# PIC18LF67K40-breakout.net
KiCad netlist of a schematic drawn in EAGLE
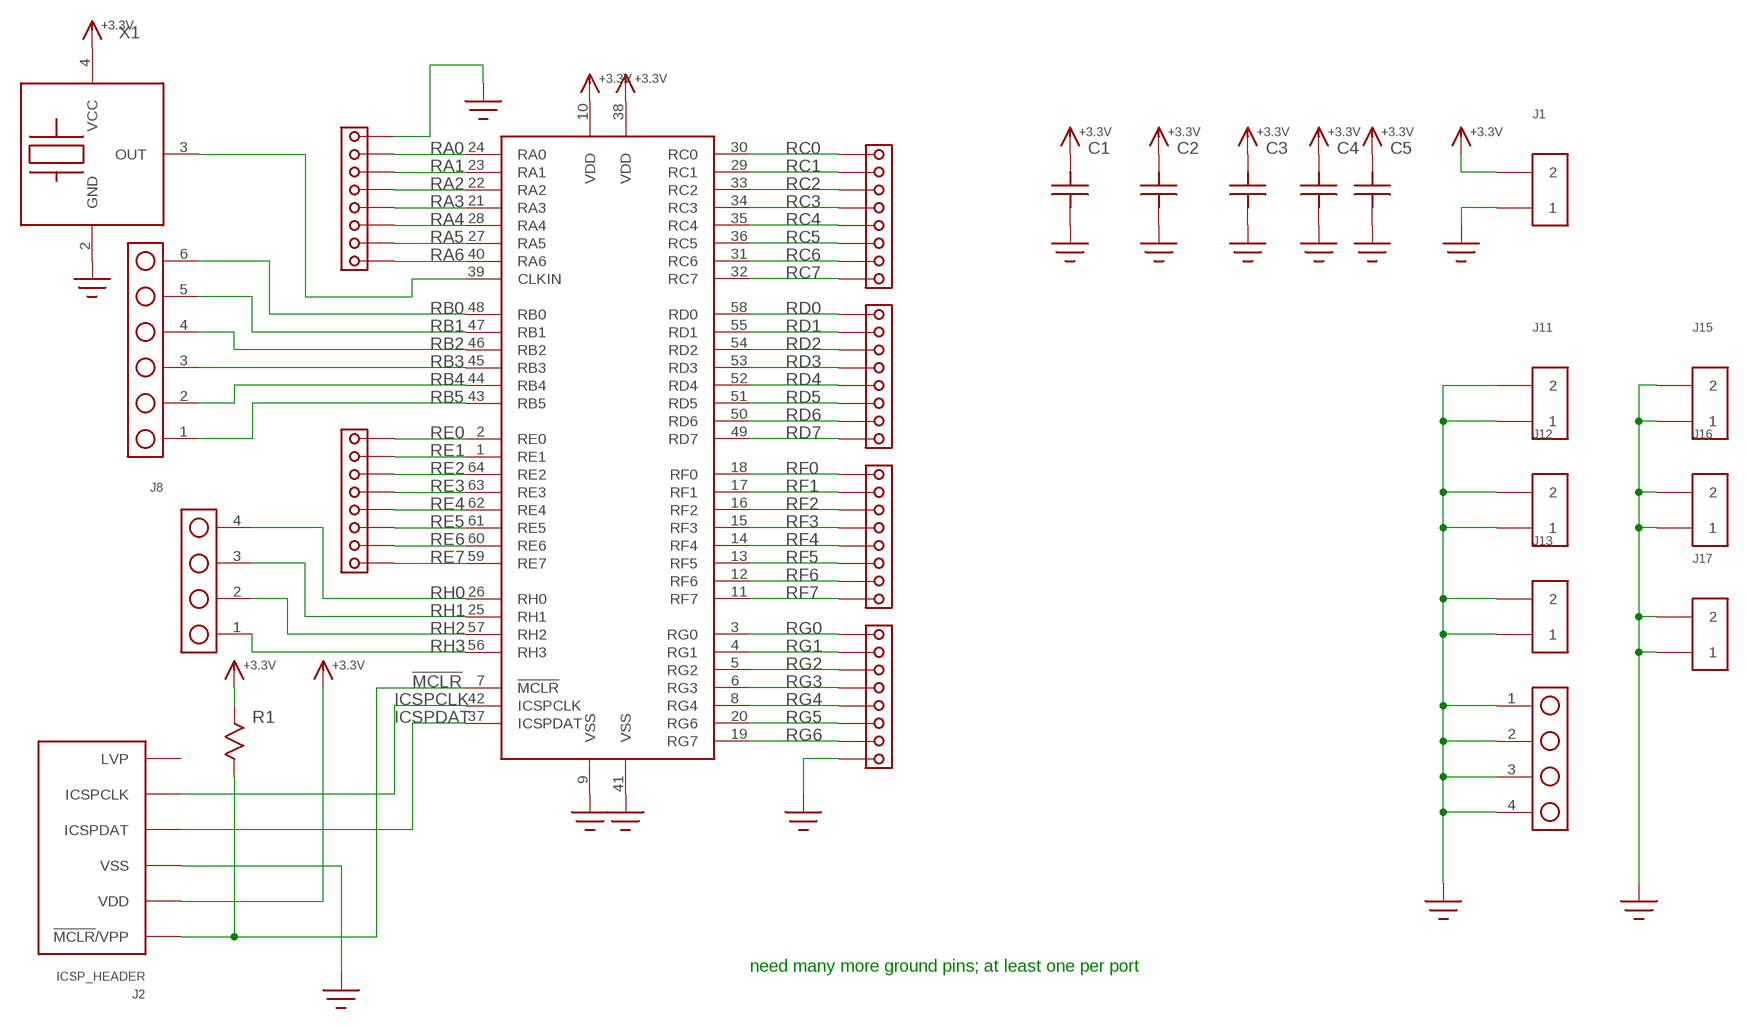
[diagram p0: schematic, sheet 1]

(export (version "E")
  (design (tool "Eeschema 10.0.6"))
  (components
    (comp (ref "C1")
      (value "C1206")
      (footprint "eagle-import:1206")
      (libsource (lib "eagle-import") (part "C1206"))
    )
    (comp (ref "C2")
      (value "C1206")
      (footprint "eagle-import:1206")
      (libsource (lib "eagle-import") (part "C1206"))
    )
    (comp (ref "C3")
      (value "C0603")
      (footprint "eagle-import:C0603")
      (libsource (lib "eagle-import") (part "C0603"))
    )
    (comp (ref "C4")
      (value "C0603")
      (footprint "eagle-import:C0603")
      (libsource (lib "eagle-import") (part "C0603"))
    )
    (comp (ref "C5")
      (value "C0603")
      (footprint "eagle-import:C0603")
      (libsource (lib "eagle-import") (part "C0603"))
    )
    (comp (ref "IC1")
      (value "PIC18LF67K40")
      (footprint "eagle-import:TQFP-100-10X10")
      (libsource (lib "eagle-import") (part "PIC18LF67K40"))
    )
    (comp (ref "J1")
      (value "HEADER_2PIN")
      (footprint "eagle-import:HEADER_2PIN")
      (libsource (lib "eagle-import") (part "HEADER_2PIN"))
    )
    (comp (ref "J2")
      (value "ICSP_HEADER")
      (footprint "eagle-import:HEADER_6PIN")
      (libsource (lib "eagle-import") (part "ICSP_HEADER"))
    )
    (comp (ref "J3")
      (value "HEADER_8PIN_TIGHT")
      (footprint "eagle-import:HEADER_8_PIN")
      (libsource (lib "eagle-import") (part "HEADER_8PIN_TIGHT"))
    )
    (comp (ref "J4")
      (value "HEADER_8PIN_TIGHT")
      (footprint "eagle-import:HEADER_8_PIN")
      (libsource (lib "eagle-import") (part "HEADER_8PIN_TIGHT"))
    )
    (comp (ref "J5")
      (value "HEADER_8PIN_TIGHT")
      (footprint "eagle-import:HEADER_8_PIN")
      (libsource (lib "eagle-import") (part "HEADER_8PIN_TIGHT"))
    )
    (comp (ref "J6")
      (value "HEADER_8PIN_TIGHT")
      (footprint "eagle-import:HEADER_8_PIN")
      (libsource (lib "eagle-import") (part "HEADER_8PIN_TIGHT"))
    )
    (comp (ref "J7")
      (value "HEADER_8PIN_TIGHT")
      (footprint "eagle-import:HEADER_8_PIN")
      (libsource (lib "eagle-import") (part "HEADER_8PIN_TIGHT"))
    )
    (comp (ref "J8")
      (value "HEADER_6PIN")
      (footprint "eagle-import:HEADER_6PIN")
      (libsource (lib "eagle-import") (part "HEADER_6PIN"))
    )
    (comp (ref "J9")
      (value "HEADER_4PIN")
      (footprint "eagle-import:HEADER_4PIN")
      (libsource (lib "eagle-import") (part "HEADER_4PIN"))
    )
    (comp (ref "J10")
      (value "HEADER_8PIN_TIGHT")
      (footprint "eagle-import:HEADER_8_PIN")
      (libsource (lib "eagle-import") (part "HEADER_8PIN_TIGHT"))
    )
    (comp (ref "J11")
      (value "HEADER_2PIN")
      (footprint "eagle-import:HEADER_2PIN")
      (libsource (lib "eagle-import") (part "HEADER_2PIN"))
    )
    (comp (ref "J12")
      (value "HEADER_2PIN")
      (footprint "eagle-import:HEADER_2PIN")
      (libsource (lib "eagle-import") (part "HEADER_2PIN"))
    )
    (comp (ref "J13")
      (value "HEADER_2PIN")
      (footprint "eagle-import:HEADER_2PIN")
      (libsource (lib "eagle-import") (part "HEADER_2PIN"))
    )
    (comp (ref "J14")
      (value "HEADER_4PIN")
      (footprint "eagle-import:HEADER_4PIN")
      (libsource (lib "eagle-import") (part "HEADER_4PIN"))
    )
    (comp (ref "J15")
      (value "HEADER_2PIN")
      (footprint "eagle-import:HEADER_2PIN")
      (libsource (lib "eagle-import") (part "HEADER_2PIN"))
    )
    (comp (ref "J16")
      (value "HEADER_2PIN")
      (footprint "eagle-import:HEADER_2PIN")
      (libsource (lib "eagle-import") (part "HEADER_2PIN"))
    )
    (comp (ref "J17")
      (value "HEADER_2PIN")
      (footprint "eagle-import:HEADER_2PIN")
      (libsource (lib "eagle-import") (part "HEADER_2PIN"))
    )
    (comp (ref "R1")
      (value "R0603")
      (footprint "eagle-import:R0603")
      (libsource (lib "eagle-import") (part "R0603"))
    )
    (comp (ref "X1")
      (value "XTAL_OSC")
      (footprint "eagle-import:XTAL_3.2X5")
      (libsource (lib "eagle-import") (part "XTAL_OSC"))
    )
  )
  (nets
    (net (code "1") (name "+3.3V") (class "Default")
      (node (ref "C1") (pin "P$2") (pinfunction "P$2_P$2") (pintype "bidirectional"))
      (node (ref "C2") (pin "P$2") (pinfunction "P$2_P$2") (pintype "bidirectional"))
      (node (ref "C3") (pin "P$2") (pinfunction "P$2_P$2") (pintype "bidirectional"))
      (node (ref "C4") (pin "P$2") (pinfunction "P$2_P$2") (pintype "bidirectional"))
      (node (ref "C5") (pin "P$2") (pinfunction "P$2_P$2") (pintype "bidirectional"))
      (node (ref "IC1") (pin "10") (pinfunction "VDD_10") (pintype "bidirectional"))
      (node (ref "IC1") (pin "38") (pinfunction "VDD_38") (pintype "bidirectional"))
      (node (ref "J1") (pin "2") (pinfunction "2_2") (pintype "bidirectional"))
      (node (ref "J2") (pin "2") (pinfunction "VDD_2") (pintype "bidirectional"))
      (node (ref "R1") (pin "P$1") (pinfunction "P$3_P$1") (pintype "bidirectional"))
      (node (ref "X1") (pin "4") (pinfunction "VCC_4") (pintype "bidirectional"))
    )
    (net (code "2") (name "/ICSPCLK") (class "Default")
      (node (ref "IC1") (pin "42") (pinfunction "ICSPCLK_42") (pintype "bidirectional"))
      (node (ref "J2") (pin "5") (pinfunction "ICSPCLK_5") (pintype "bidirectional"))
    )
    (net (code "3") (name "/ICSPDAT") (class "Default")
      (node (ref "IC1") (pin "37") (pinfunction "ICSPDAT_37") (pintype "bidirectional"))
      (node (ref "J2") (pin "4") (pinfunction "ICSPDAT_4") (pintype "bidirectional"))
    )
    (net (code "4") (name "/RA0") (class "Default")
      (node (ref "IC1") (pin "24") (pinfunction "RA0_24") (pintype "bidirectional"))
      (node (ref "J6") (pin "7") (pinfunction "7_7") (pintype "bidirectional"))
    )
    (net (code "5") (name "/RA1") (class "Default")
      (node (ref "IC1") (pin "23") (pinfunction "RA1_23") (pintype "bidirectional"))
      (node (ref "J6") (pin "6") (pinfunction "6_6") (pintype "bidirectional"))
    )
    (net (code "6") (name "/RA2") (class "Default")
      (node (ref "IC1") (pin "22") (pinfunction "RA2_22") (pintype "bidirectional"))
      (node (ref "J6") (pin "5") (pinfunction "5_5") (pintype "bidirectional"))
    )
    (net (code "7") (name "/RA3") (class "Default")
      (node (ref "IC1") (pin "21") (pinfunction "RA3_21") (pintype "bidirectional"))
      (node (ref "J6") (pin "4") (pinfunction "4_4") (pintype "bidirectional"))
    )
    (net (code "8") (name "/RA4") (class "Default")
      (node (ref "IC1") (pin "28") (pinfunction "RA4_28") (pintype "bidirectional"))
      (node (ref "J6") (pin "3") (pinfunction "3_3") (pintype "bidirectional"))
    )
    (net (code "9") (name "/RA5") (class "Default")
      (node (ref "IC1") (pin "27") (pinfunction "RA5_27") (pintype "bidirectional"))
      (node (ref "J6") (pin "2") (pinfunction "2_2") (pintype "bidirectional"))
    )
    (net (code "10") (name "/RA6") (class "Default")
      (node (ref "IC1") (pin "40") (pinfunction "RA6_40") (pintype "bidirectional"))
      (node (ref "J6") (pin "1") (pinfunction "1_1") (pintype "bidirectional"))
    )
    (net (code "11") (name "/RB0") (class "Default")
      (node (ref "IC1") (pin "48") (pinfunction "RB0_48") (pintype "bidirectional"))
      (node (ref "J8") (pin "6") (pinfunction "6_6") (pintype "bidirectional"))
    )
    (net (code "12") (name "/RB1") (class "Default")
      (node (ref "IC1") (pin "47") (pinfunction "RB1_47") (pintype "bidirectional"))
      (node (ref "J8") (pin "5") (pinfunction "5_5") (pintype "bidirectional"))
    )
    (net (code "13") (name "/RB2") (class "Default")
      (node (ref "IC1") (pin "46") (pinfunction "RB2_46") (pintype "bidirectional"))
      (node (ref "J8") (pin "4") (pinfunction "4_4") (pintype "bidirectional"))
    )
    (net (code "14") (name "/RB3") (class "Default")
      (node (ref "IC1") (pin "45") (pinfunction "RB3_45") (pintype "bidirectional"))
      (node (ref "J8") (pin "3") (pinfunction "3_3") (pintype "bidirectional"))
    )
    (net (code "15") (name "/RB4") (class "Default")
      (node (ref "IC1") (pin "44") (pinfunction "RB4_44") (pintype "bidirectional"))
      (node (ref "J8") (pin "2") (pinfunction "2_2") (pintype "bidirectional"))
    )
    (net (code "16") (name "/RB5") (class "Default")
      (node (ref "IC1") (pin "43") (pinfunction "RB5_43") (pintype "bidirectional"))
      (node (ref "J8") (pin "1") (pinfunction "1_1") (pintype "bidirectional"))
    )
    (net (code "17") (name "/RC0") (class "Default")
      (node (ref "IC1") (pin "30") (pinfunction "RC0_30") (pintype "bidirectional"))
      (node (ref "J3") (pin "1") (pinfunction "1_1") (pintype "bidirectional"))
    )
    (net (code "18") (name "/RC1") (class "Default")
      (node (ref "IC1") (pin "29") (pinfunction "RC1_29") (pintype "bidirectional"))
      (node (ref "J3") (pin "2") (pinfunction "2_2") (pintype "bidirectional"))
    )
    (net (code "19") (name "/RC2") (class "Default")
      (node (ref "IC1") (pin "33") (pinfunction "RC2_33") (pintype "bidirectional"))
      (node (ref "J3") (pin "3") (pinfunction "3_3") (pintype "bidirectional"))
    )
    (net (code "20") (name "/RC3") (class "Default")
      (node (ref "IC1") (pin "34") (pinfunction "RC3_34") (pintype "bidirectional"))
      (node (ref "J3") (pin "4") (pinfunction "4_4") (pintype "bidirectional"))
    )
    (net (code "21") (name "/RC4") (class "Default")
      (node (ref "IC1") (pin "35") (pinfunction "RC4_35") (pintype "bidirectional"))
      (node (ref "J3") (pin "5") (pinfunction "5_5") (pintype "bidirectional"))
    )
    (net (code "22") (name "/RC5") (class "Default")
      (node (ref "IC1") (pin "36") (pinfunction "RC5_36") (pintype "bidirectional"))
      (node (ref "J3") (pin "6") (pinfunction "6_6") (pintype "bidirectional"))
    )
    (net (code "23") (name "/RC6") (class "Default")
      (node (ref "IC1") (pin "31") (pinfunction "RC6_31") (pintype "bidirectional"))
      (node (ref "J3") (pin "7") (pinfunction "7_7") (pintype "bidirectional"))
    )
    (net (code "24") (name "/RC7") (class "Default")
      (node (ref "IC1") (pin "32") (pinfunction "RC7_32") (pintype "bidirectional"))
      (node (ref "J3") (pin "8") (pinfunction "8_8") (pintype "bidirectional"))
    )
    (net (code "25") (name "/RD0") (class "Default")
      (node (ref "IC1") (pin "58") (pinfunction "RD0_58") (pintype "bidirectional"))
      (node (ref "J4") (pin "1") (pinfunction "1_1") (pintype "bidirectional"))
    )
    (net (code "26") (name "/RD1") (class "Default")
      (node (ref "IC1") (pin "55") (pinfunction "RD1_55") (pintype "bidirectional"))
      (node (ref "J4") (pin "2") (pinfunction "2_2") (pintype "bidirectional"))
    )
    (net (code "27") (name "/RD2") (class "Default")
      (node (ref "IC1") (pin "54") (pinfunction "RD2_54") (pintype "bidirectional"))
      (node (ref "J4") (pin "3") (pinfunction "3_3") (pintype "bidirectional"))
    )
    (net (code "28") (name "/RD3") (class "Default")
      (node (ref "IC1") (pin "53") (pinfunction "RD3_53") (pintype "bidirectional"))
      (node (ref "J4") (pin "4") (pinfunction "4_4") (pintype "bidirectional"))
    )
    (net (code "29") (name "/RD4") (class "Default")
      (node (ref "IC1") (pin "52") (pinfunction "RD4_52") (pintype "bidirectional"))
      (node (ref "J4") (pin "5") (pinfunction "5_5") (pintype "bidirectional"))
    )
    (net (code "30") (name "/RD5") (class "Default")
      (node (ref "IC1") (pin "51") (pinfunction "RD5_51") (pintype "bidirectional"))
      (node (ref "J4") (pin "6") (pinfunction "6_6") (pintype "bidirectional"))
    )
    (net (code "31") (name "/RD6") (class "Default")
      (node (ref "IC1") (pin "50") (pinfunction "RD6_50") (pintype "bidirectional"))
      (node (ref "J4") (pin "7") (pinfunction "7_7") (pintype "bidirectional"))
    )
    (net (code "32") (name "/RD7") (class "Default")
      (node (ref "IC1") (pin "49") (pinfunction "RD7_49") (pintype "bidirectional"))
      (node (ref "J4") (pin "8") (pinfunction "8_8") (pintype "bidirectional"))
    )
    (net (code "33") (name "/RE0") (class "Default")
      (node (ref "IC1") (pin "2") (pinfunction "RE0_2") (pintype "bidirectional"))
      (node (ref "J7") (pin "8") (pinfunction "8_8") (pintype "bidirectional"))
    )
    (net (code "34") (name "/RE1") (class "Default")
      (node (ref "IC1") (pin "1") (pinfunction "RE1_1") (pintype "bidirectional"))
      (node (ref "J7") (pin "7") (pinfunction "7_7") (pintype "bidirectional"))
    )
    (net (code "35") (name "/RE2") (class "Default")
      (node (ref "IC1") (pin "64") (pinfunction "RE2_64") (pintype "bidirectional"))
      (node (ref "J7") (pin "6") (pinfunction "6_6") (pintype "bidirectional"))
    )
    (net (code "36") (name "/RE3") (class "Default")
      (node (ref "IC1") (pin "63") (pinfunction "RE3_63") (pintype "bidirectional"))
      (node (ref "J7") (pin "5") (pinfunction "5_5") (pintype "bidirectional"))
    )
    (net (code "37") (name "/RE4") (class "Default")
      (node (ref "IC1") (pin "62") (pinfunction "RE4_62") (pintype "bidirectional"))
      (node (ref "J7") (pin "4") (pinfunction "4_4") (pintype "bidirectional"))
    )
    (net (code "38") (name "/RE5") (class "Default")
      (node (ref "IC1") (pin "61") (pinfunction "RE5_61") (pintype "bidirectional"))
      (node (ref "J7") (pin "3") (pinfunction "3_3") (pintype "bidirectional"))
    )
    (net (code "39") (name "/RE6") (class "Default")
      (node (ref "IC1") (pin "60") (pinfunction "RE6_60") (pintype "bidirectional"))
      (node (ref "J7") (pin "2") (pinfunction "2_2") (pintype "bidirectional"))
    )
    (net (code "40") (name "/RE7") (class "Default")
      (node (ref "IC1") (pin "59") (pinfunction "RE7_59") (pintype "bidirectional"))
      (node (ref "J7") (pin "1") (pinfunction "1_1") (pintype "bidirectional"))
    )
    (net (code "41") (name "/RF0") (class "Default")
      (node (ref "IC1") (pin "18") (pinfunction "RF0_18") (pintype "bidirectional"))
      (node (ref "J5") (pin "1") (pinfunction "1_1") (pintype "bidirectional"))
    )
    (net (code "42") (name "/RF1") (class "Default")
      (node (ref "IC1") (pin "17") (pinfunction "RF1_17") (pintype "bidirectional"))
      (node (ref "J5") (pin "2") (pinfunction "2_2") (pintype "bidirectional"))
    )
    (net (code "43") (name "/RF2") (class "Default")
      (node (ref "IC1") (pin "16") (pinfunction "RF2_16") (pintype "bidirectional"))
      (node (ref "J5") (pin "3") (pinfunction "3_3") (pintype "bidirectional"))
    )
    (net (code "44") (name "/RF3") (class "Default")
      (node (ref "IC1") (pin "15") (pinfunction "RF3_15") (pintype "bidirectional"))
      (node (ref "J5") (pin "4") (pinfunction "4_4") (pintype "bidirectional"))
    )
    (net (code "45") (name "/RF4") (class "Default")
      (node (ref "IC1") (pin "14") (pinfunction "RF4_14") (pintype "bidirectional"))
      (node (ref "J5") (pin "5") (pinfunction "5_5") (pintype "bidirectional"))
    )
    (net (code "46") (name "/RF5") (class "Default")
      (node (ref "IC1") (pin "13") (pinfunction "RF5_13") (pintype "bidirectional"))
      (node (ref "J5") (pin "6") (pinfunction "6_6") (pintype "bidirectional"))
    )
    (net (code "47") (name "/RF6") (class "Default")
      (node (ref "IC1") (pin "12") (pinfunction "RF6_12") (pintype "bidirectional"))
      (node (ref "J5") (pin "7") (pinfunction "7_7") (pintype "bidirectional"))
    )
    (net (code "48") (name "/RF7") (class "Default")
      (node (ref "IC1") (pin "11") (pinfunction "RF7_11") (pintype "bidirectional"))
      (node (ref "J5") (pin "8") (pinfunction "8_8") (pintype "bidirectional"))
    )
    (net (code "49") (name "/RG0") (class "Default")
      (node (ref "IC1") (pin "3") (pinfunction "RG0_3") (pintype "bidirectional"))
      (node (ref "J10") (pin "1") (pinfunction "1_1") (pintype "bidirectional"))
    )
    (net (code "50") (name "/RG1") (class "Default")
      (node (ref "IC1") (pin "4") (pinfunction "RG1_4") (pintype "bidirectional"))
      (node (ref "J10") (pin "2") (pinfunction "2_2") (pintype "bidirectional"))
    )
    (net (code "51") (name "/RG2") (class "Default")
      (node (ref "IC1") (pin "5") (pinfunction "RG2_5") (pintype "bidirectional"))
      (node (ref "J10") (pin "3") (pinfunction "3_3") (pintype "bidirectional"))
    )
    (net (code "52") (name "/RG3") (class "Default")
      (node (ref "IC1") (pin "6") (pinfunction "RG3_6") (pintype "bidirectional"))
      (node (ref "J10") (pin "4") (pinfunction "4_4") (pintype "bidirectional"))
    )
    (net (code "53") (name "/RG4") (class "Default")
      (node (ref "IC1") (pin "8") (pinfunction "RG4_8") (pintype "bidirectional"))
      (node (ref "J10") (pin "5") (pinfunction "5_5") (pintype "bidirectional"))
    )
    (net (code "54") (name "/RG5") (class "Default")
      (node (ref "IC1") (pin "20") (pinfunction "RG6_20") (pintype "bidirectional"))
      (node (ref "J10") (pin "6") (pinfunction "6_6") (pintype "bidirectional"))
    )
    (net (code "55") (name "/RG6") (class "Default")
      (node (ref "IC1") (pin "19") (pinfunction "RG7_19") (pintype "bidirectional"))
      (node (ref "J10") (pin "7") (pinfunction "7_7") (pintype "bidirectional"))
    )
    (net (code "56") (name "/RH0") (class "Default")
      (node (ref "IC1") (pin "26") (pinfunction "RH0_26") (pintype "bidirectional"))
      (node (ref "J9") (pin "4") (pinfunction "4_4") (pintype "bidirectional"))
    )
    (net (code "57") (name "/RH1") (class "Default")
      (node (ref "IC1") (pin "25") (pinfunction "RH1_25") (pintype "bidirectional"))
      (node (ref "J9") (pin "3") (pinfunction "3_3") (pintype "bidirectional"))
    )
    (net (code "58") (name "/RH2") (class "Default")
      (node (ref "IC1") (pin "57") (pinfunction "RH2_57") (pintype "bidirectional"))
      (node (ref "J9") (pin "2") (pinfunction "2_2") (pintype "bidirectional"))
    )
    (net (code "59") (name "/RH3") (class "Default")
      (node (ref "IC1") (pin "56") (pinfunction "RH3_56") (pintype "bidirectional"))
      (node (ref "J9") (pin "1") (pinfunction "1_1") (pintype "bidirectional"))
    )
    (net (code "60") (name "/~{MCLR}") (class "Default")
      (node (ref "IC1") (pin "7") (pinfunction "~{MCLR}_7") (pintype "bidirectional"))
      (node (ref "J2") (pin "1") (pinfunction "~{MCLR}/VPP_1") (pintype "bidirectional"))
      (node (ref "R1") (pin "P$2") (pinfunction "P$4_P$2") (pintype "bidirectional"))
    )
    (net (code "61") (name "GND") (class "Default")
      (node (ref "C1") (pin "P$1") (pinfunction "P$1_P$1") (pintype "bidirectional"))
      (node (ref "C2") (pin "P$1") (pinfunction "P$1_P$1") (pintype "bidirectional"))
      (node (ref "C3") (pin "P$1") (pinfunction "P$1_P$1") (pintype "bidirectional"))
      (node (ref "C4") (pin "P$1") (pinfunction "P$1_P$1") (pintype "bidirectional"))
      (node (ref "C5") (pin "P$1") (pinfunction "P$1_P$1") (pintype "bidirectional"))
      (node (ref "IC1") (pin "41") (pinfunction "VSS_41") (pintype "bidirectional"))
      (node (ref "IC1") (pin "9") (pinfunction "VSS_9") (pintype "bidirectional"))
      (node (ref "J1") (pin "1") (pinfunction "1_1") (pintype "bidirectional"))
      (node (ref "J10") (pin "8") (pinfunction "8_8") (pintype "bidirectional"))
      (node (ref "J11") (pin "1") (pinfunction "1_1") (pintype "bidirectional"))
      (node (ref "J11") (pin "2") (pinfunction "2_2") (pintype "bidirectional"))
      (node (ref "J12") (pin "1") (pinfunction "1_1") (pintype "bidirectional"))
      (node (ref "J12") (pin "2") (pinfunction "2_2") (pintype "bidirectional"))
      (node (ref "J13") (pin "1") (pinfunction "1_1") (pintype "bidirectional"))
      (node (ref "J13") (pin "2") (pinfunction "2_2") (pintype "bidirectional"))
      (node (ref "J14") (pin "1") (pinfunction "1_1") (pintype "bidirectional"))
      (node (ref "J14") (pin "2") (pinfunction "2_2") (pintype "bidirectional"))
      (node (ref "J14") (pin "3") (pinfunction "3_3") (pintype "bidirectional"))
      (node (ref "J14") (pin "4") (pinfunction "4_4") (pintype "bidirectional"))
      (node (ref "J15") (pin "1") (pinfunction "1_1") (pintype "bidirectional"))
      (node (ref "J15") (pin "2") (pinfunction "2_2") (pintype "bidirectional"))
      (node (ref "J16") (pin "1") (pinfunction "1_1") (pintype "bidirectional"))
      (node (ref "J16") (pin "2") (pinfunction "2_2") (pintype "bidirectional"))
      (node (ref "J17") (pin "1") (pinfunction "1_1") (pintype "bidirectional"))
      (node (ref "J17") (pin "2") (pinfunction "2_2") (pintype "bidirectional"))
      (node (ref "J2") (pin "3") (pinfunction "VSS_3") (pintype "bidirectional"))
      (node (ref "J6") (pin "8") (pinfunction "8_8") (pintype "bidirectional"))
      (node (ref "X1") (pin "2") (pinfunction "GND_2") (pintype "bidirectional"))
    )
    (net (code "62") (name "Net-(IC1-CLKIN)") (class "Default")
      (node (ref "IC1") (pin "39") (pinfunction "CLKIN_39") (pintype "bidirectional"))
      (node (ref "X1") (pin "3") (pinfunction "OUT_3") (pintype "bidirectional"))
    )
    (net (code "63") (name "unconnected-(J2-LVP-Pad6)") (class "Default")
      (node (ref "J2") (pin "6") (pinfunction "LVP_6") (pintype "bidirectional"))
    )
  )
)
